# Spannungsversorgung.net
KiCad netlist of a schematic drawn in EAGLE
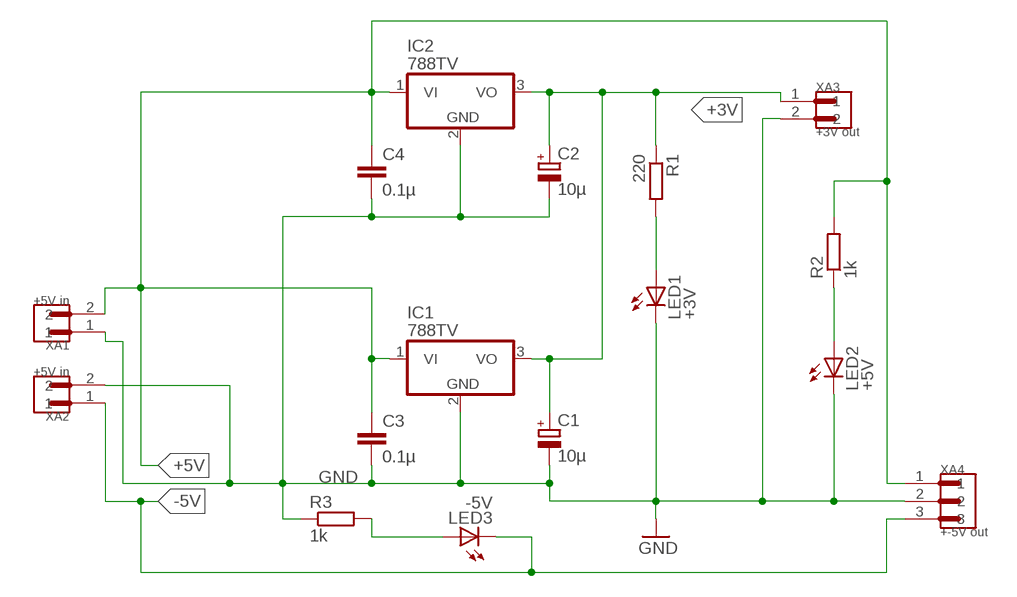
[diagram p0: schematic, sheet 1]

(export (version "E")
  (design (tool "Eeschema 10.0.6"))
  (components
    (comp (ref "C1")
      (value "10µ")
      (footprint "eagle-import:E2,5-6")
      (libsource (lib "eagle-import") (part "CPOL-EUE2.5-6"))
    )
    (comp (ref "C2")
      (value "10µ")
      (footprint "eagle-import:E2,5-6")
      (libsource (lib "eagle-import") (part "CPOL-EUE2.5-6"))
    )
    (comp (ref "C3")
      (value "0.1µ")
      (footprint "eagle-import:C2.5-3")
      (libsource (lib "eagle-import") (part "C2,5-3"))
    )
    (comp (ref "C4")
      (value "0.1µ")
      (footprint "eagle-import:C2.5-3")
      (libsource (lib "eagle-import") (part "C2,5-3"))
    )
    (comp (ref "IC1")
      (value "788TV")
      (footprint "eagle-import:TO220V")
      (libsource (lib "eagle-import") (part "78TV8"))
    )
    (comp (ref "IC2")
      (value "788TV")
      (footprint "eagle-import:TO220V")
      (libsource (lib "eagle-import") (part "78TV8"))
    )
    (comp (ref "LED1")
      (value "+3V")
      (footprint "eagle-import:LED3MM")
      (fields (field (name "MF") "VISHAY SEMICONDUCTOR"))
      (libsource (lib "eagle-import") (part "TLLG4400"))
    )
    (comp (ref "LED2")
      (value "+5V")
      (footprint "eagle-import:LED3MM")
      (fields (field (name "MF") "VISHAY SEMICONDUCTOR"))
      (libsource (lib "eagle-import") (part "TLLG4400"))
    )
    (comp (ref "LED3")
      (value "-5V")
      (footprint "eagle-import:LED3MM")
      (fields (field (name "MF") "VISHAY SEMICONDUCTOR"))
      (libsource (lib "eagle-import") (part "TLLG4400"))
    )
    (comp (ref "R1")
      (value "220")
      (footprint "eagle-import:0207_7")
      (libsource (lib "eagle-import") (part "R-EU_0207/7"))
    )
    (comp (ref "R2")
      (value "1k")
      (footprint "eagle-import:0207_7")
      (libsource (lib "eagle-import") (part "R-EU_0207/7"))
    )
    (comp (ref "R3")
      (value "1k")
      (footprint "eagle-import:0207_7")
      (libsource (lib "eagle-import") (part "R-EU_0207/7"))
    )
    (comp (ref "XA1")
      (value "+5V in")
      (footprint "eagle-import:JST_B2P-VH(LF)(SN)")
      (fields (field (name "MF") "JST") (field (name "MP") "B2P-VH_LF__SN_"))
      (libsource (lib "eagle-import") (part "B2P-VH(LF)(SN)"))
    )
    (comp (ref "XA2")
      (value "+5V in")
      (footprint "eagle-import:JST_B2P-VH(LF)(SN)")
      (fields (field (name "MF") "JST") (field (name "MP") "B2P-VH_LF__SN_"))
      (libsource (lib "eagle-import") (part "B2P-VH(LF)(SN)"))
    )
    (comp (ref "XA3")
      (value "+3V out")
      (footprint "eagle-import:JST_B2P-VH(LF)(SN)")
      (fields (field (name "MF") "JST") (field (name "MP") "B2P-VH_LF__SN_"))
      (libsource (lib "eagle-import") (part "B2P-VH(LF)(SN)"))
    )
    (comp (ref "XA4")
      (value "+-5V out")
      (footprint "eagle-import:JST_B3P-VH(LF)(SN)")
      (fields (field (name "MF") "JST") (field (name "MP") "B3P-VH_LF__SN_"))
      (libsource (lib "eagle-import") (part "B3P-VH(LF)(SN)"))
    )
  )
  (nets
    (net (code "1") (name "+3V") (class "Default")
      (node (ref "C1") (pin "+") (pinfunction "+_+") (pintype "passive"))
      (node (ref "C2") (pin "+") (pinfunction "+_+") (pintype "passive"))
      (node (ref "IC1") (pin "3") (pinfunction "VO_3") (pintype "passive"))
      (node (ref "IC2") (pin "3") (pinfunction "VO_3") (pintype "passive"))
      (node (ref "R1") (pin "1") (pinfunction "1_1") (pintype "passive"))
      (node (ref "XA3") (pin "1") (pinfunction "1_1") (pintype "passive"))
    )
    (net (code "2") (name "+5V") (class "Default")
      (node (ref "C3") (pin "1") (pinfunction "1_1") (pintype "passive"))
      (node (ref "C4") (pin "1") (pinfunction "1_1") (pintype "passive"))
      (node (ref "IC1") (pin "1") (pinfunction "VI_1") (pintype "input"))
      (node (ref "IC2") (pin "1") (pinfunction "VI_1") (pintype "input"))
      (node (ref "R2") (pin "2") (pinfunction "2_2") (pintype "passive"))
      (node (ref "XA1") (pin "2") (pinfunction "2_2") (pintype "passive"))
      (node (ref "XA4") (pin "1") (pinfunction "1_1") (pintype "passive"))
    )
    (net (code "3") (name "-5V") (class "Default")
      (node (ref "LED3") (pin "K") (pinfunction "C_K") (pintype "passive"))
      (node (ref "XA2") (pin "1") (pinfunction "1_1") (pintype "passive"))
      (node (ref "XA4") (pin "3") (pinfunction "3_3") (pintype "passive"))
    )
    (net (code "4") (name "GND") (class "Default")
      (node (ref "C1") (pin "-") (pinfunction "-_-") (pintype "passive"))
      (node (ref "C2") (pin "-") (pinfunction "-_-") (pintype "passive"))
      (node (ref "C3") (pin "2") (pinfunction "2_2") (pintype "passive"))
      (node (ref "C4") (pin "2") (pinfunction "2_2") (pintype "passive"))
      (node (ref "IC1") (pin "2") (pinfunction "GND_2") (pintype "passive"))
      (node (ref "IC2") (pin "2") (pinfunction "GND_2") (pintype "passive"))
      (node (ref "LED1") (pin "K") (pinfunction "C_K") (pintype "passive"))
      (node (ref "LED2") (pin "K") (pinfunction "C_K") (pintype "passive"))
      (node (ref "R3") (pin "1") (pinfunction "1_1") (pintype "passive"))
      (node (ref "XA1") (pin "1") (pinfunction "1_1") (pintype "passive"))
      (node (ref "XA2") (pin "2") (pinfunction "2_2") (pintype "passive"))
      (node (ref "XA3") (pin "2") (pinfunction "2_2") (pintype "passive"))
      (node (ref "XA4") (pin "2") (pinfunction "2_2") (pintype "passive"))
    )
    (net (code "5") (name "Net-(LED1-PadA)") (class "Default")
      (node (ref "LED1") (pin "A") (pinfunction "A_A") (pintype "passive"))
      (node (ref "R1") (pin "2") (pinfunction "2_2") (pintype "passive"))
    )
    (net (code "6") (name "Net-(LED2-PadA)") (class "Default")
      (node (ref "LED2") (pin "A") (pinfunction "A_A") (pintype "passive"))
      (node (ref "R2") (pin "1") (pinfunction "1_1") (pintype "passive"))
    )
    (net (code "7") (name "Net-(LED3-PadA)") (class "Default")
      (node (ref "LED3") (pin "A") (pinfunction "A_A") (pintype "passive"))
      (node (ref "R3") (pin "2") (pinfunction "2_2") (pintype "passive"))
    )
  )
)
